# HeadSheet.net
KiCad netlist of a schematic drawn in Altium Designer
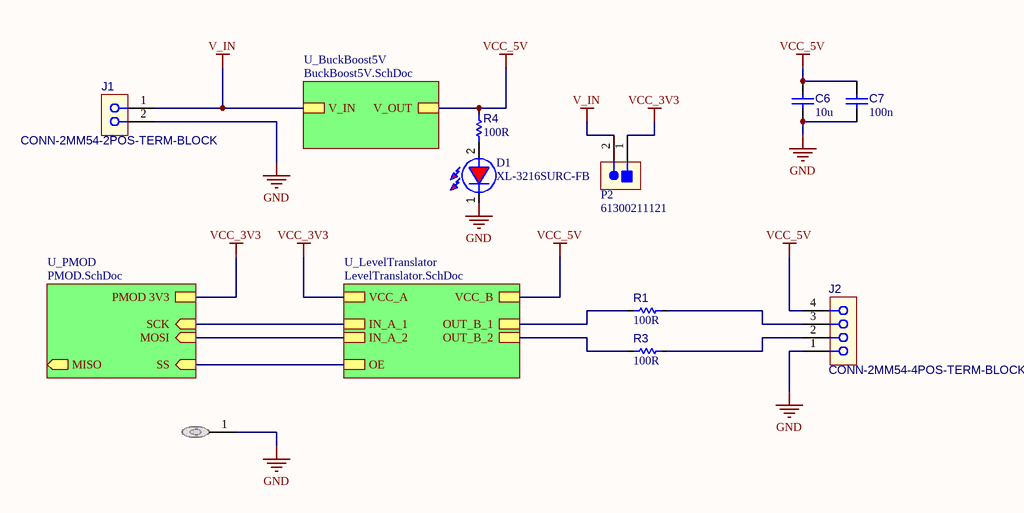
[diagram p0: HeadSheet.SchDoc]

(export (version "E")
  (design (tool "Eeschema 10.0.6"))
  (components
    (comp (ref "C6")
      (value "10u")
      (footprint "C_2012[0805]")
      (description "Capacitor type 1")
      (fields (field (name "TOLERANCE") "10%") (field (name "Comment") "CAP CER 10uF 10V X7R 0805"))
      (libsource (lib "TEP-AltiumLib-Passives-RLC") (part "capacitor"))
    )
    (comp (ref "C7")
      (value "100n")
      (footprint "C_1608[0603]")
      (description "Capacitor type 1")
      (fields (field (name "TOLERANCE") "10%") (field (name "Comment") "CAP CER 100nF 50V 0603"))
      (libsource (lib "TEP-AltiumLib-Passives-RLC") (part "capacitor"))
    )
    (comp (ref "D1")
      (value "XL-3216SURC-FB")
      (footprint "LED 1206")
      (description "DEL Rouge 1206")
      (libsource (lib "TEP-AltiumLib-Discretes") (part "D_LED_RED_1206"))
    )
    (comp (ref "J1")
      (value "CONN-2MM54-2POS-TERM-BLOCK")
      (footprint "CONN_TERM_BLOCK_2POS_100MIL")
      (description "CONN TERM BLOCK 2POS 100mil pitch")
      (libsource (lib "TEP-AltiumLib-Connectors") (part "CONN-2MM54-2POS-TERM-BLOCK"))
    )
    (comp (ref "J2")
      (value "CONN-2MM54-4POS-TERM-BLOCK")
      (footprint "CONN_TERM_BLOCK_4POS_100MIL")
      (description "CONN TERM BLOCK 4POS 100mil pitch")
      (libsource (lib "TEP-AltiumLib-Connectors") (part "CONN-2MM54-4POS-TERM-BLOCK"))
    )
    (comp (ref "MH1")
      (value "DNP")
      (footprint "MP_M-Hole_#4-40_LOOSE-FIT")
      (description "Mounting Hole #4-40 w/ Flat Washer")
      (libsource (lib "TEP-AltiumLib-Hardware") (part "MH-4-40"))
    )
    (comp (ref "P2")
      (value "61300211121")
      (footprint "CONN_HDR_2POS_100MILS_TH")
      (description "CONN HEADER 2POS 100MIL")
      (libsource (lib "TEP-AltiumLib-Connectors") (part "CONN-100MIL-HDR-01X02"))
    )
    (comp (ref "R1")
      (value "100R")
      (footprint "R_1608[0603]")
      (description "Resistor type 1")
      (fields (field (name "TOLERANCE") "1%") (field (name "Comment") "Res 100R 1% 0603"))
      (libsource (lib "TEP-AltiumLib-Passives-RLC") (part "resistor"))
    )
    (comp (ref "R3")
      (value "100R")
      (footprint "R_1608[0603]")
      (description "Resistor type 1")
      (fields (field (name "TOLERANCE") "1%") (field (name "Comment") "Res 100R 1% 0603"))
      (libsource (lib "TEP-AltiumLib-Passives-RLC") (part "resistor"))
    )
    (comp (ref "R4")
      (value "100R")
      (footprint "R_1608[0603]")
      (description "Resistor type 1")
      (fields (field (name "TOLERANCE") "1%") (field (name "Comment") "Res 100R 1% 0603"))
      (libsource (lib "TEP-AltiumLib-Passives-RLC") (part "resistor"))
    )
  )
  (nets
    (net (code "5") (name "/OUT_B_1") (class "Default")
      (node (ref "R1") (pin "1") (pinfunction "1_1") (pintype "passive"))
    )
    (net (code "6") (name "/OUT_B_2") (class "Default")
      (node (ref "R3") (pin "1") (pinfunction "1_1") (pintype "passive"))
    )
    (net (code "7") (name "GND") (class "Default")
      (node (ref "C6") (pin "1") (pinfunction "1_1") (pintype "passive"))
      (node (ref "C7") (pin "1") (pinfunction "1_1") (pintype "passive"))
      (node (ref "D1") (pin "1") (pinfunction "K_1") (pintype "passive"))
      (node (ref "J1") (pin "2") (pinfunction "2_2") (pintype "passive"))
      (node (ref "J2") (pin "1") (pinfunction "1_1") (pintype "passive"))
      (node (ref "MH1") (pin "1") (pinfunction "1_1") (pintype "power_in"))
    )
    (net (code "8") (name "Net-(D1-A)") (class "Default")
      (node (ref "D1") (pin "2") (pinfunction "A_2") (pintype "passive"))
      (node (ref "R4") (pin "1") (pinfunction "1_1") (pintype "passive"))
    )
    (net (code "9") (name "Net-(J2-Pad2)") (class "Default")
      (node (ref "J2") (pin "2") (pinfunction "2_2") (pintype "passive"))
      (node (ref "R3") (pin "2") (pinfunction "2_2") (pintype "passive"))
    )
    (net (code "10") (name "Net-(J2-Pad3)") (class "Default")
      (node (ref "J2") (pin "3") (pinfunction "3_3") (pintype "passive"))
      (node (ref "R1") (pin "2") (pinfunction "2_2") (pintype "passive"))
    )
    (net (code "11") (name "VCC_3V3") (class "Default")
      (node (ref "P2") (pin "1") (pinfunction "1_1") (pintype "passive"))
    )
    (net (code "12") (name "VCC_5V") (class "Default")
      (node (ref "C6") (pin "2") (pinfunction "2_2") (pintype "passive"))
      (node (ref "C7") (pin "2") (pinfunction "2_2") (pintype "passive"))
      (node (ref "J2") (pin "4") (pinfunction "4_4") (pintype "passive"))
      (node (ref "R4") (pin "2") (pinfunction "2_2") (pintype "passive"))
    )
    (net (code "13") (name "V_IN") (class "Default")
      (node (ref "J1") (pin "1") (pinfunction "1_1") (pintype "passive"))
      (node (ref "P2") (pin "2") (pinfunction "2_2") (pintype "passive"))
    )
  )
)
